# ADP1614_BREAKOUT.net
KiCad netlist of a schematic drawn in EAGLE
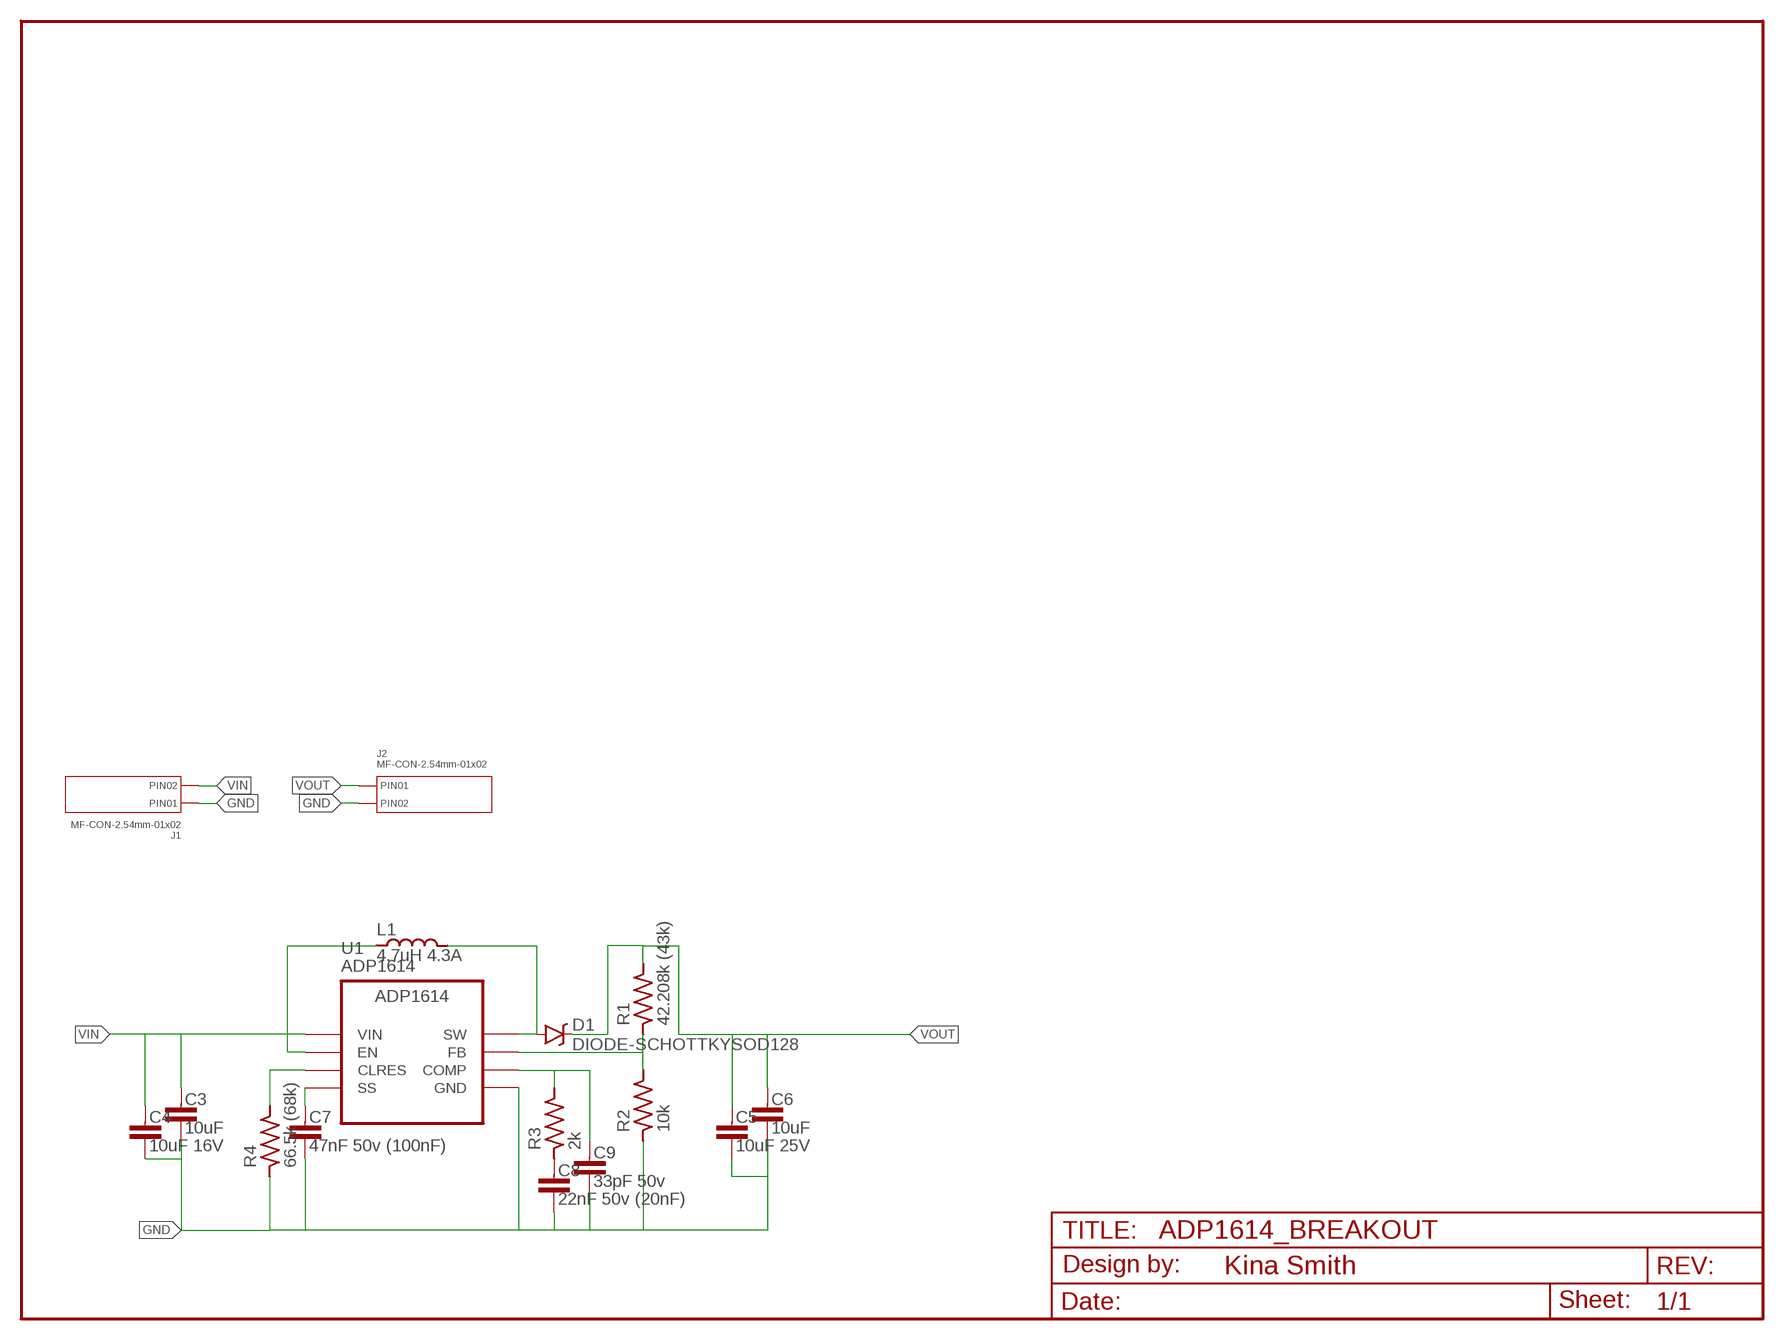
[diagram p0: schematic, sheet 1]

(export (version "E")
  (design (tool "Eeschema 10.0.6"))
  (components
    (comp (ref "C3")
      (value "10uF")
      (footprint "eagle-import:C0805-N")
      (libsource (lib "eagle-import") (part "CAPACITOR_NP0805-N"))
    )
    (comp (ref "C4")
      (value "10uF 16V")
      (footprint "eagle-import:C0805-N")
      (libsource (lib "eagle-import") (part "CAPACITOR_NP0805-N"))
    )
    (comp (ref "C5")
      (value "10uF 25V")
      (footprint "eagle-import:C0805-N")
      (libsource (lib "eagle-import") (part "CAPACITOR_NP0805-N"))
    )
    (comp (ref "C6")
      (value "10uF")
      (footprint "eagle-import:C0805-N")
      (libsource (lib "eagle-import") (part "CAPACITOR_NP0805-N"))
    )
    (comp (ref "C7")
      (value "47nF 50v (100nF)")
      (footprint "eagle-import:C0603-N")
      (libsource (lib "eagle-import") (part "CAPACITOR_NP0603-N"))
    )
    (comp (ref "C8")
      (value "22nF 50v (20nF)")
      (footprint "eagle-import:C0603-N")
      (libsource (lib "eagle-import") (part "CAPACITOR_NP0603-N"))
    )
    (comp (ref "C9")
      (value "33pF 50v")
      (footprint "eagle-import:C0603-N")
      (libsource (lib "eagle-import") (part "CAPACITOR_NP0603-N"))
    )
    (comp (ref "D1")
      (value "DIODE-SCHOTTKYSOD128")
      (footprint "eagle-import:SOD128")
      (libsource (lib "eagle-import") (part "DIODE-SCHOTTKYSOD128"))
    )
    (comp (ref "FRAME1")
      (value "FRAME-LETTER")
      (footprint "eagle-import:CREATIVE_COMMONS")
      (libsource (lib "eagle-import") (part "FRAME-LETTER"))
    )
    (comp (ref "J1")
      (value "MF-CON-2.54mm-01x02")
      (footprint "eagle-import:PTH_2.54MM_01X02")
      (fields (field (name "HOUSEPART") "YES"))
      (libsource (lib "eagle-import") (part "CON_01X02_PTH_2.54MM"))
    )
    (comp (ref "J2")
      (value "MF-CON-2.54mm-01x02")
      (footprint "eagle-import:PTH_2.54MM_01X02")
      (fields (field (name "HOUSEPART") "YES"))
      (libsource (lib "eagle-import") (part "CON_01X02_PTH_2.54MM"))
    )
    (comp (ref "L1")
      (value "4.7uH 4.3A")
      (footprint "eagle-import:L8080")
      (fields (field (name "PARTNO") "NRS8040T100MJGJ"))
      (libsource (lib "eagle-import") (part "INDUCTOR8080"))
    )
    (comp (ref "R1")
      (value "42.208k (43k)")
      (footprint "eagle-import:R0603-N")
      (libsource (lib "eagle-import") (part "RESISTOR0603-N"))
    )
    (comp (ref "R2")
      (value "10k")
      (footprint "eagle-import:R0603-N")
      (libsource (lib "eagle-import") (part "RESISTOR0603-N"))
    )
    (comp (ref "R3")
      (value "2k")
      (footprint "eagle-import:R0603-N")
      (libsource (lib "eagle-import") (part "RESISTOR0603-N"))
    )
    (comp (ref "R4")
      (value "66.5k (68k)")
      (footprint "eagle-import:R0603-N")
      (libsource (lib "eagle-import") (part "RESISTOR0603-N"))
    )
    (comp (ref "U1")
      (value "ADP1614")
      (footprint "eagle-import:DFN300X300X80-11N")
      (libsource (lib "eagle-import") (part "ADP1614"))
    )
  )
  (nets
    (net (code "1") (name "GND") (class "Default")
      (node (ref "C3") (pin "2") (pinfunction "2_2") (pintype "passive"))
      (node (ref "C4") (pin "2") (pinfunction "2_2") (pintype "passive"))
      (node (ref "C5") (pin "2") (pinfunction "2_2") (pintype "passive"))
      (node (ref "C6") (pin "2") (pinfunction "2_2") (pintype "passive"))
      (node (ref "C7") (pin "2") (pinfunction "2_2") (pintype "passive"))
      (node (ref "C8") (pin "2") (pinfunction "2_2") (pintype "passive"))
      (node (ref "C9") (pin "2") (pinfunction "2_2") (pintype "passive"))
      (node (ref "J1") (pin "P$1") (pinfunction "PIN1_P$1") (pintype "bidirectional"))
      (node (ref "J2") (pin "P$2") (pinfunction "PIN2_P$2") (pintype "bidirectional"))
      (node (ref "R2") (pin "1") (pinfunction "P$1_1") (pintype "passive"))
      (node (ref "R4") (pin "1") (pinfunction "P$1_1") (pintype "passive"))
      (node (ref "U1") (pin "11") (pinfunction "GND_11") (pintype "bidirectional"))
      (node (ref "U1") (pin "4") (pinfunction "GND_4") (pintype "bidirectional"))
      (node (ref "U1") (pin "5") (pinfunction "GND_5") (pintype "bidirectional"))
    )
    (net (code "2") (name "Net-(D1-A)") (class "Default")
      (node (ref "D1") (pin "A-2") (pinfunction "A_A-2") (pintype "passive"))
      (node (ref "L1") (pin "2") (pinfunction "P$2_2") (pintype "passive"))
      (node (ref "U1") (pin "6") (pinfunction "SW_6") (pintype "bidirectional"))
      (node (ref "U1") (pin "7") (pinfunction "SW_7") (pintype "bidirectional"))
    )
    (net (code "3") (name "Net-(R1-P$1)") (class "Default")
      (node (ref "R1") (pin "1") (pinfunction "P$1_1") (pintype "passive"))
      (node (ref "R2") (pin "2") (pinfunction "P$2_2") (pintype "passive"))
      (node (ref "U1") (pin "2") (pinfunction "FB_2") (pintype "bidirectional"))
    )
    (net (code "4") (name "Net-(R3-P$1)") (class "Default")
      (node (ref "C8") (pin "1") (pinfunction "1_1") (pintype "passive"))
      (node (ref "R3") (pin "1") (pinfunction "P$1_1") (pintype "passive"))
    )
    (net (code "5") (name "Net-(R3-P$2)") (class "Default")
      (node (ref "C9") (pin "1") (pinfunction "1_1") (pintype "passive"))
      (node (ref "R3") (pin "2") (pinfunction "P$2_2") (pintype "passive"))
      (node (ref "U1") (pin "1") (pinfunction "COMP_1") (pintype "bidirectional"))
    )
    (net (code "6") (name "Net-(R4-P$2)") (class "Default")
      (node (ref "R4") (pin "2") (pinfunction "P$2_2") (pintype "passive"))
      (node (ref "U1") (pin "9") (pinfunction "CLRES_9") (pintype "bidirectional"))
    )
    (net (code "7") (name "Net-(U1-SS)") (class "Default")
      (node (ref "C7") (pin "1") (pinfunction "1_1") (pintype "passive"))
      (node (ref "U1") (pin "10") (pinfunction "SS_10") (pintype "bidirectional"))
    )
    (net (code "8") (name "VIN") (class "Default")
      (node (ref "C3") (pin "1") (pinfunction "1_1") (pintype "passive"))
      (node (ref "C4") (pin "1") (pinfunction "1_1") (pintype "passive"))
      (node (ref "J1") (pin "P$2") (pinfunction "PIN2_P$2") (pintype "bidirectional"))
      (node (ref "L1") (pin "1") (pinfunction "P$1_1") (pintype "passive"))
      (node (ref "U1") (pin "3") (pinfunction "EN_3") (pintype "bidirectional"))
      (node (ref "U1") (pin "8") (pinfunction "VIN_8") (pintype "bidirectional"))
    )
    (net (code "9") (name "VOUT") (class "Default")
      (node (ref "C5") (pin "1") (pinfunction "1_1") (pintype "passive"))
      (node (ref "C6") (pin "1") (pinfunction "1_1") (pintype "passive"))
      (node (ref "D1") (pin "C-1") (pinfunction "C_C-1") (pintype "passive"))
      (node (ref "J2") (pin "P$1") (pinfunction "PIN1_P$1") (pintype "bidirectional"))
      (node (ref "R1") (pin "2") (pinfunction "P$2_2") (pintype "passive"))
    )
  )
)
